# blinker.net
KiCad netlist of a schematic drawn in EAGLE
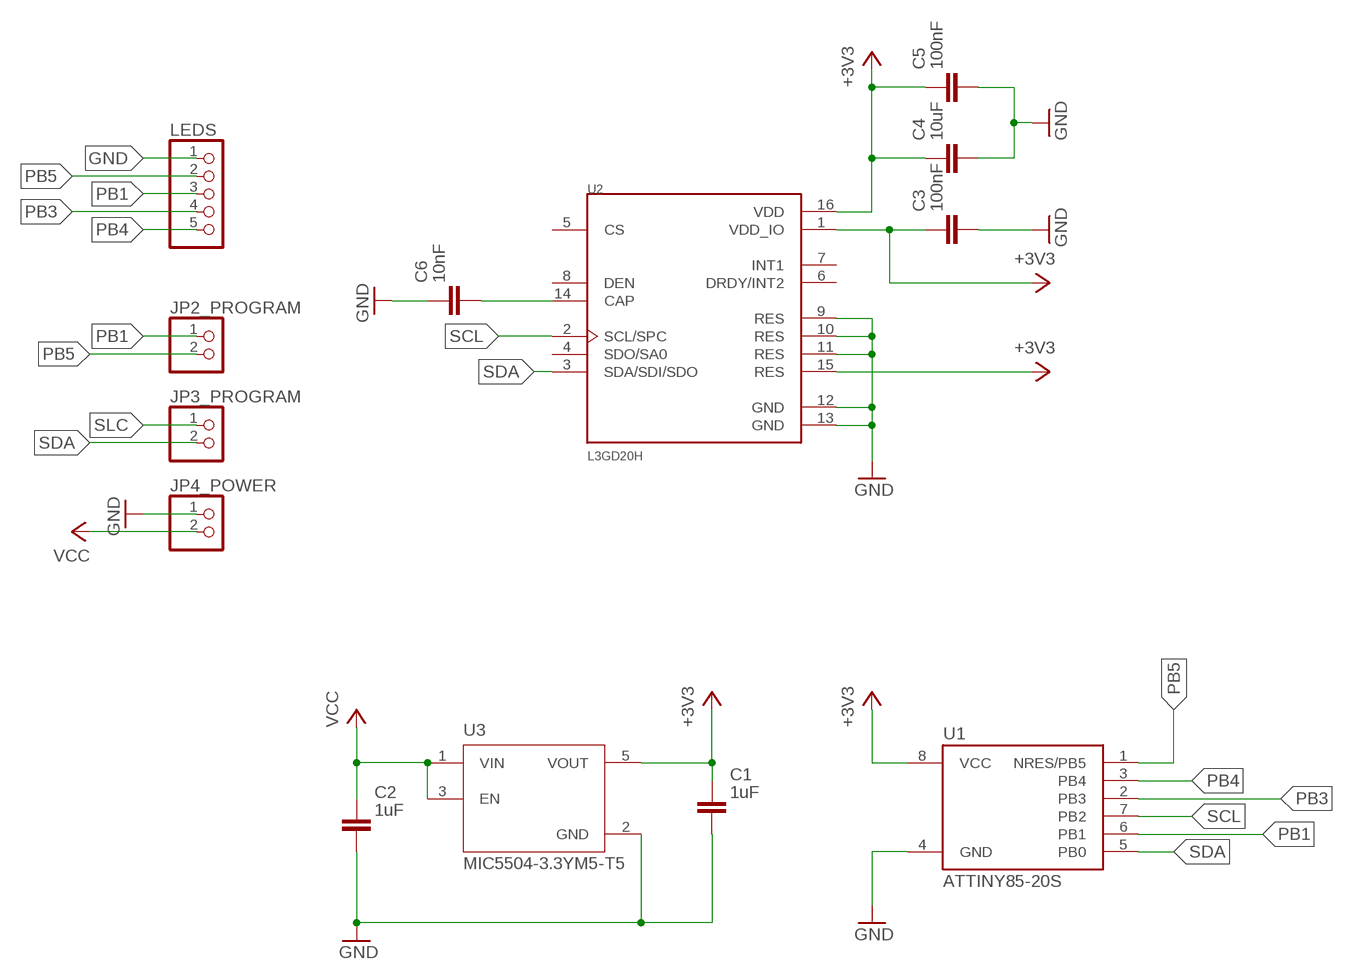
[diagram p0: schematic, sheet 1]

(export (version "E")
  (design (tool "Eeschema 10.0.6"))
  (components
    (comp (ref "C1")
      (value "1uF")
      (footprint "eagle-import:CAPC3216X135")
      (libsource (lib "eagle-import") (part "CCHIP-1206(3216-METRIC)_"))
    )
    (comp (ref "C2")
      (value "1uF")
      (footprint "eagle-import:CAPC3216X135")
      (libsource (lib "eagle-import") (part "CCHIP-1206(3216-METRIC)_"))
    )
    (comp (ref "C3")
      (value "100nF")
      (footprint "eagle-import:CAPC3216X135")
      (libsource (lib "eagle-import") (part "CCHIP-1206(3216-METRIC)_"))
    )
    (comp (ref "C4")
      (value "10uF")
      (footprint "eagle-import:CAPC3216X135")
      (libsource (lib "eagle-import") (part "CCHIP-1206(3216-METRIC)_"))
    )
    (comp (ref "C5")
      (value "100nF")
      (footprint "eagle-import:CAPC3216X135")
      (libsource (lib "eagle-import") (part "CCHIP-1206(3216-METRIC)_"))
    )
    (comp (ref "C6")
      (value "10nF")
      (footprint "eagle-import:CAPC3216X135")
      (libsource (lib "eagle-import") (part "CCHIP-1206(3216-METRIC)_"))
    )
    (comp (ref "JP2_PROGRAM")
      (value "PINHD-1X2/90")
      (footprint "eagle-import:1X02_90")
      (libsource (lib "eagle-import") (part "PINHD-1X2/90"))
    )
    (comp (ref "JP3_PROGRAM")
      (value "PINHD-1X2/90")
      (footprint "eagle-import:1X02_90")
      (libsource (lib "eagle-import") (part "PINHD-1X2/90"))
    )
    (comp (ref "JP4_POWER")
      (value "PINHD-1X2/90")
      (footprint "eagle-import:1X02_90")
      (libsource (lib "eagle-import") (part "PINHD-1X2/90"))
    )
    (comp (ref "LEDS")
      (value "PINHD-1X5/90")
      (footprint "eagle-import:1X05_90")
      (libsource (lib "eagle-import") (part "PINHD-1X5/90"))
    )
    (comp (ref "U1")
      (value "ATTINY85-20S")
      (footprint "eagle-import:SOIC8_EIAJ_208MIL")
      (libsource (lib "eagle-import") (part "ATTINY85S-20"))
    )
    (comp (ref "U2")
      (value "L3GD20H")
      (footprint "eagle-import:LGA16R50P7X5_300X300X100")
      (fields (field (name "MF") "STMicroelectronics"))
      (libsource (lib "eagle-import") (part "L3GD20H"))
    )
    (comp (ref "U3")
      (value "MIC5504-3.3YM5-T5")
      (footprint "eagle-import:SOT95P280X145-5N")
      (fields (field (name "MF") "Microchip"))
      (libsource (lib "eagle-import") (part "MIC5504-3.3YM5-T5"))
    )
  )
  (nets
    (net (code "1") (name "+3V3") (class "Default")
      (node (ref "C1") (pin "1") (pinfunction "1_1") (pintype "passive"))
      (node (ref "C3") (pin "1") (pinfunction "1_1") (pintype "passive"))
      (node (ref "C4") (pin "1") (pinfunction "1_1") (pintype "passive"))
      (node (ref "C5") (pin "1") (pinfunction "1_1") (pintype "passive"))
      (node (ref "U1") (pin "8") (pinfunction "VCC_8") (pintype "power_in"))
      (node (ref "U2") (pin "1") (pinfunction "VDD_IO_1") (pintype "power_in"))
      (node (ref "U2") (pin "15") (pinfunction "RES_15") (pintype "power_in"))
      (node (ref "U2") (pin "16") (pinfunction "VDD_16") (pintype "power_in"))
      (node (ref "U3") (pin "5") (pinfunction "VOUT_5") (pintype "output"))
    )
    (net (code "2") (name "GND") (class "Default")
      (node (ref "C1") (pin "2") (pinfunction "2_2") (pintype "passive"))
      (node (ref "C2") (pin "2") (pinfunction "2_2") (pintype "passive"))
      (node (ref "C3") (pin "2") (pinfunction "2_2") (pintype "passive"))
      (node (ref "C4") (pin "2") (pinfunction "2_2") (pintype "passive"))
      (node (ref "C5") (pin "2") (pinfunction "2_2") (pintype "passive"))
      (node (ref "C6") (pin "1") (pinfunction "1_1") (pintype "passive"))
      (node (ref "JP4_POWER") (pin "1") (pinfunction "1_1") (pintype "passive"))
      (node (ref "LEDS") (pin "1") (pinfunction "1_1") (pintype "passive"))
      (node (ref "U1") (pin "4") (pinfunction "GND_4") (pintype "power_in"))
      (node (ref "U2") (pin "10") (pinfunction "RES_10") (pintype "power_in"))
      (node (ref "U2") (pin "11") (pinfunction "RES_11") (pintype "power_in"))
      (node (ref "U2") (pin "12") (pinfunction "GND_12") (pintype "power_in"))
      (node (ref "U2") (pin "13") (pinfunction "GND_13") (pintype "power_in"))
      (node (ref "U2") (pin "9") (pinfunction "RES_9") (pintype "power_in"))
      (node (ref "U3") (pin "2") (pinfunction "GND_2") (pintype "power_in"))
    )
    (net (code "3") (name "Net-(U2-CAP)") (class "Default")
      (node (ref "C6") (pin "2") (pinfunction "2_2") (pintype "passive"))
      (node (ref "U2") (pin "14") (pinfunction "CAP_14") (pintype "passive"))
    )
    (net (code "4") (name "PB1") (class "Default")
      (node (ref "JP2_PROGRAM") (pin "1") (pinfunction "1_1") (pintype "passive"))
      (node (ref "LEDS") (pin "3") (pinfunction "3_3") (pintype "passive"))
      (node (ref "U1") (pin "6") (pinfunction "PB1_6") (pintype "bidirectional"))
    )
    (net (code "5") (name "PB3") (class "Default")
      (node (ref "LEDS") (pin "4") (pinfunction "4_4") (pintype "passive"))
      (node (ref "U1") (pin "2") (pinfunction "PB3_2") (pintype "bidirectional"))
    )
    (net (code "6") (name "PB4") (class "Default")
      (node (ref "LEDS") (pin "5") (pinfunction "5_5") (pintype "passive"))
      (node (ref "U1") (pin "3") (pinfunction "PB4_3") (pintype "bidirectional"))
    )
    (net (code "7") (name "PB5") (class "Default")
      (node (ref "JP2_PROGRAM") (pin "2") (pinfunction "2_2") (pintype "passive"))
      (node (ref "LEDS") (pin "2") (pinfunction "2_2") (pintype "passive"))
      (node (ref "U1") (pin "1") (pinfunction "NRES/PB5_1") (pintype "bidirectional"))
    )
    (net (code "8") (name "SCL") (class "Default")
      (node (ref "U1") (pin "7") (pinfunction "PB2_7") (pintype "bidirectional"))
      (node (ref "U2") (pin "2") (pinfunction "SCL/SPC_2") (pintype "input"))
    )
    (net (code "9") (name "SDA") (class "Default")
      (node (ref "JP3_PROGRAM") (pin "2") (pinfunction "2_2") (pintype "passive"))
      (node (ref "U1") (pin "5") (pinfunction "PB0_5") (pintype "bidirectional"))
      (node (ref "U2") (pin "3") (pinfunction "SDA/SDI/SDO_3") (pintype "bidirectional"))
    )
    (net (code "10") (name "SLC") (class "Default")
      (node (ref "JP3_PROGRAM") (pin "1") (pinfunction "1_1") (pintype "passive"))
    )
    (net (code "11") (name "VCC") (class "Default")
      (node (ref "C2") (pin "1") (pinfunction "1_1") (pintype "passive"))
      (node (ref "JP4_POWER") (pin "2") (pinfunction "2_2") (pintype "passive"))
      (node (ref "U3") (pin "1") (pinfunction "VIN_1") (pintype "input"))
      (node (ref "U3") (pin "3") (pinfunction "EN_3") (pintype "input"))
    )
    (net (code "12") (name "unconnected-(U2-CS-Pad5)") (class "Default")
      (node (ref "U2") (pin "5") (pinfunction "CS_5") (pintype "input"))
    )
    (net (code "13") (name "unconnected-(U2-DEN-Pad8)") (class "Default")
      (node (ref "U2") (pin "8") (pinfunction "DEN_8") (pintype "input"))
    )
    (net (code "14") (name "unconnected-(U2-DRDY{slash}INT2-Pad6)") (class "Default")
      (node (ref "U2") (pin "6") (pinfunction "DRDY/INT2_6") (pintype "output"))
    )
    (net (code "15") (name "unconnected-(U2-INT1-Pad7)") (class "Default")
      (node (ref "U2") (pin "7") (pinfunction "INT1_7") (pintype "output"))
    )
    (net (code "16") (name "unconnected-(U2-SDO{slash}SA0-Pad4)") (class "Default")
      (node (ref "U2") (pin "4") (pinfunction "SDO/SA0_4") (pintype "bidirectional"))
    )
  )
)
